# Power_Distribution_-_Solar_Sense_Telemet.net
KiCad netlist of a schematic drawn in Altium Designer
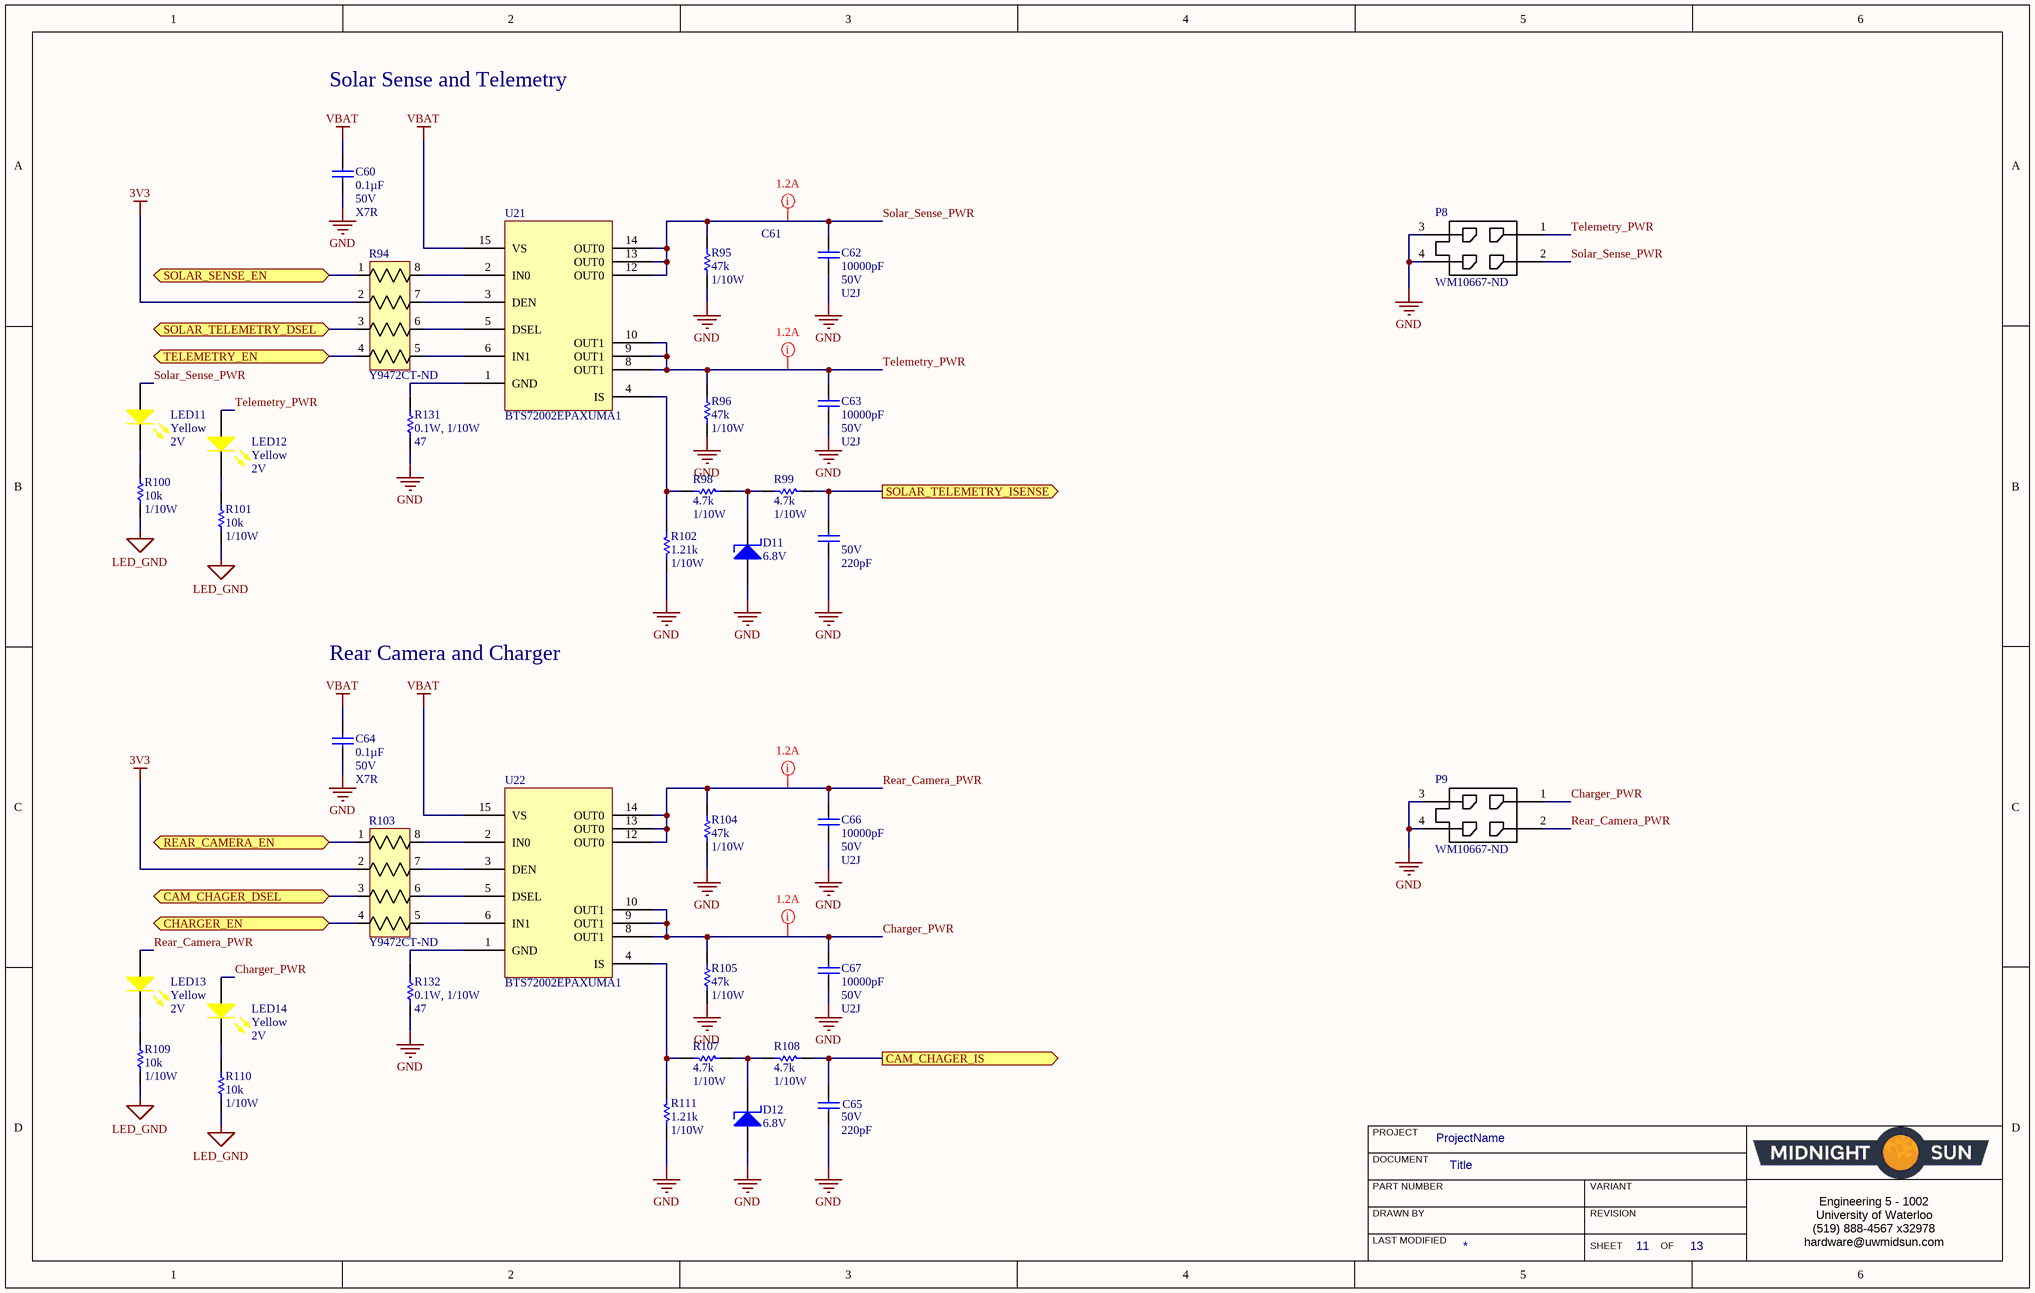
[diagram p0: Power Distribution - Solar Sense, Telemetry, Rear Camera, and Charger.SchDoc]

(export (version "E")
  (design (tool "Eeschema 10.0.6"))
  (components
    (comp (ref "C60")
      (value "CAP CER 0.1UF 50V 10% X7R 0603")
      (footprint "CAP, 0603")
      (description "0.10µF ±10% 50V Ceramic Capacitor X7R 0603 (1608 Metric)")
      (fields
        (field (name "TOLERANCE") "±10%")
        (field (name "CAPACITANCE") "0.1µF")
        (field (name "VOLTAGE") "50V")
        (field (name "TEMPERATURE COEFFICIENT") "X7R")
      )
      (libsource (lib "Schematic Diagrams") (part "CAP CER 0.1UF 50V 10% X7R 0603"))
    )
    (comp (ref "C61")
      (value "CAP CER 220PF 50V C0G/NP0 0603")
      (footprint "CAP, 0603")
      (description "220pF ±5% 50V Ceramic Capacitor C0G, NP0 0603 (1608 Metric)")
      (fields
        (field (name "MANUFACTURER") "KEMET")
        (field (name "TOLERANCE") "5%")
        (field (name "VOLTAGE RATING") "50V")
        (field (name "CAPACITANCE") "220pF")
      )
      (libsource (lib "Schematic Diagrams") (part "CAP CER 220PF 50V C0G/NP0 0603"))
    )
    (comp (ref "C62")
      (value "CAP CER 10nF 50V 5% X7R 0603")
      (footprint "CAP, 0603")
      (description "10000pF ±5% 50V Ceramic Capacitor U2J 0603 (1608 Metric)")
      (fields
        (field (name "TOLERANCE") "±5%")
        (field (name "CAPACITANCE") "10000pF")
        (field (name "VOLTAGE") "50V")
        (field (name "TEMPERATURE COEFFICIENT") "U2J")
      )
      (libsource (lib "Schematic Diagrams") (part "CAP CER 10nF 50V 5% X7R 0603"))
    )
    (comp (ref "C63")
      (value "CAP CER 10nF 50V 5% X7R 0603")
      (footprint "CAP, 0603")
      (description "10000pF ±5% 50V Ceramic Capacitor U2J 0603 (1608 Metric)")
      (fields
        (field (name "TOLERANCE") "±5%")
        (field (name "CAPACITANCE") "10000pF")
        (field (name "VOLTAGE") "50V")
        (field (name "TEMPERATURE COEFFICIENT") "U2J")
      )
      (libsource (lib "Schematic Diagrams") (part "CAP CER 10nF 50V 5% X7R 0603"))
    )
    (comp (ref "C64")
      (value "CAP CER 0.1UF 50V 10% X7R 0603")
      (footprint "CAP, 0603")
      (description "0.10µF ±10% 50V Ceramic Capacitor X7R 0603 (1608 Metric)")
      (fields
        (field (name "TOLERANCE") "±10%")
        (field (name "CAPACITANCE") "0.1µF")
        (field (name "VOLTAGE") "50V")
        (field (name "TEMPERATURE COEFFICIENT") "X7R")
      )
      (libsource (lib "Schematic Diagrams") (part "CAP CER 0.1UF 50V 10% X7R 0603"))
    )
    (comp (ref "C65")
      (value "CAP CER 220PF 50V C0G/NP0 0603")
      (footprint "CAP, 0603")
      (description "220pF ±5% 50V Ceramic Capacitor C0G, NP0 0603 (1608 Metric)")
      (fields
        (field (name "MANUFACTURER") "KEMET")
        (field (name "TOLERANCE") "5%")
        (field (name "VOLTAGE RATING") "50V")
        (field (name "CAPACITANCE") "220pF")
      )
      (libsource (lib "Schematic Diagrams") (part "CAP CER 220PF 50V C0G/NP0 0603"))
    )
    (comp (ref "C66")
      (value "CAP CER 10nF 50V 5% X7R 0603")
      (footprint "CAP, 0603")
      (description "10000pF ±5% 50V Ceramic Capacitor U2J 0603 (1608 Metric)")
      (fields
        (field (name "TOLERANCE") "±5%")
        (field (name "CAPACITANCE") "10000pF")
        (field (name "VOLTAGE") "50V")
        (field (name "TEMPERATURE COEFFICIENT") "U2J")
      )
      (libsource (lib "Schematic Diagrams") (part "CAP CER 10nF 50V 5% X7R 0603"))
    )
    (comp (ref "C67")
      (value "CAP CER 10nF 50V 5% X7R 0603")
      (footprint "CAP, 0603")
      (description "10000pF ±5% 50V Ceramic Capacitor U2J 0603 (1608 Metric)")
      (fields
        (field (name "TOLERANCE") "±5%")
        (field (name "CAPACITANCE") "10000pF")
        (field (name "VOLTAGE") "50V")
        (field (name "TEMPERATURE COEFFICIENT") "U2J")
      )
      (libsource (lib "Schematic Diagrams") (part "CAP CER 10nF 50V 5% X7R 0603"))
    )
    (comp (ref "D11")
      (value "6.8V")
      (footprint "DIODE SOD123")
      (description "Zener Diode 6.8V 500mW ±5% Surface Mount SOD-123")
      (fields (field (name "MANUFACTURER") "Diodes Incorporated") (field (name "TOLERANCE") "±5%"))
      (libsource (lib "Schematic Diagrams") (part "DIODE ZENER 6.8V 500MW SOD123"))
    )
    (comp (ref "D12")
      (value "6.8V")
      (footprint "DIODE SOD123")
      (description "Zener Diode 6.8V 500mW ±5% Surface Mount SOD-123")
      (fields (field (name "MANUFACTURER") "Diodes Incorporated") (field (name "TOLERANCE") "±5%"))
      (libsource (lib "Schematic Diagrams") (part "DIODE ZENER 6.8V 500MW SOD123"))
    )
    (comp (ref "LED11")
      (value "LED YELLOW CLEAR 2.1V 0603")
      (footprint "LED_0603")
      (description "Yellow 590nm LED Indication - Discrete 2V 0603 (1608 Metric)")
      (fields
        (field (name "MANUFACTURER") "Wurth Electronics Inc.")
        (field (name "MANUFACTURER PART NUMBER") "150060YS75000")
        (field (name "COLOR") "Yellow")
        (field (name "VOLTAGE - FORWARD (VF) (TYP)") "2V")
      )
      (libsource (lib "Schematic Diagrams") (part "LED YELLOW CLEAR 2.1V 0603"))
    )
    (comp (ref "LED12")
      (value "LED YELLOW CLEAR 2.1V 0603")
      (footprint "LED_0603")
      (description "Yellow 590nm LED Indication - Discrete 2V 0603 (1608 Metric)")
      (fields
        (field (name "MANUFACTURER") "Wurth Electronics Inc.")
        (field (name "MANUFACTURER PART NUMBER") "150060YS75000")
        (field (name "COLOR") "Yellow")
        (field (name "VOLTAGE - FORWARD (VF) (TYP)") "2V")
      )
      (libsource (lib "Schematic Diagrams") (part "LED YELLOW CLEAR 2.1V 0603"))
    )
    (comp (ref "LED13")
      (value "LED YELLOW CLEAR 2.1V 0603")
      (footprint "LED_0603")
      (description "Yellow 590nm LED Indication - Discrete 2V 0603 (1608 Metric)")
      (fields
        (field (name "MANUFACTURER") "Wurth Electronics Inc.")
        (field (name "MANUFACTURER PART NUMBER") "150060YS75000")
        (field (name "COLOR") "Yellow")
        (field (name "VOLTAGE - FORWARD (VF) (TYP)") "2V")
      )
      (libsource (lib "Schematic Diagrams") (part "LED YELLOW CLEAR 2.1V 0603"))
    )
    (comp (ref "LED14")
      (value "LED YELLOW CLEAR 2.1V 0603")
      (footprint "LED_0603")
      (description "Yellow 590nm LED Indication - Discrete 2V 0603 (1608 Metric)")
      (fields
        (field (name "MANUFACTURER") "Wurth Electronics Inc.")
        (field (name "MANUFACTURER PART NUMBER") "150060YS75000")
        (field (name "COLOR") "Yellow")
        (field (name "VOLTAGE - FORWARD (VF) (TYP)") "2V")
      )
      (libsource (lib "Schematic Diagrams") (part "LED YELLOW CLEAR 2.1V 0603"))
    )
    (comp (ref "P8")
      (value "CONN 4POS MICRO-FIT 3mm")
      (footprint "CONN 4POS MICROFIT (2x2)")
      (fields
        (field (name "MANUFACTURER") "Molex, LLC")
        (field (name "MANUFACTURER PART NUMBER") "430450427")
        (field (name "SUPPLIER PART NUMBER 1") "WM10667-ND")
      )
      (libsource (lib "Schematic Diagrams") (part "CONN 4POS MICRO-FIT 3mm"))
    )
    (comp (ref "P9")
      (value "CONN 4POS MICRO-FIT 3mm")
      (footprint "CONN 4POS MICROFIT (2x2)")
      (fields
        (field (name "MANUFACTURER") "Molex, LLC")
        (field (name "MANUFACTURER PART NUMBER") "430450427")
        (field (name "SUPPLIER PART NUMBER 1") "WM10667-ND")
      )
      (libsource (lib "Schematic Diagrams") (part "CONN 4POS MICRO-FIT 3mm"))
    )
    (comp (ref "R94")
      (value "RES ARRAY 4 RES 4.7K OHM 1206")
      (footprint "RES ARRAY 4RES 1206")
      (fields (field (name "TOLERANCE") "±5%") (field (name "SUPPLIER PART NUMBER 1") "Y9472CT-ND"))
      (libsource (lib "Schematic Diagrams") (part "RES ARRAY 4 RES 4.7K OHM 1206"))
    )
    (comp (ref "R95")
      (value "RES 47K OHM 1% 1/10W 0603")
      (footprint "RES, 0603")
      (description "47 kOhms ±1% 0.1W, 1/10W Chip Resistor 0603 (1608 Metric) Automotive AEC-Q200 Thick Film")
      (fields
        (field (name "MANUFACTURER") "Panasonic")
        (field (name "MANUFACTURER PART NUMBER") "ERJ3EKF4702V")
        (field (name "RESISTANCE") "47k")
        (field (name "POWER RATING") "1/10W")
      )
      (libsource (lib "Schematic Diagrams") (part "RES 47K OHM 1% 1/10W 0603"))
    )
    (comp (ref "R96")
      (value "RES 47K OHM 1% 1/10W 0603")
      (footprint "RES, 0603")
      (description "47 kOhms ±1% 0.1W, 1/10W Chip Resistor 0603 (1608 Metric) Automotive AEC-Q200 Thick Film")
      (fields
        (field (name "MANUFACTURER") "Panasonic")
        (field (name "MANUFACTURER PART NUMBER") "ERJ3EKF4702V")
        (field (name "RESISTANCE") "47k")
        (field (name "POWER RATING") "1/10W")
      )
      (libsource (lib "Schematic Diagrams") (part "RES 47K OHM 1% 1/10W 0603"))
    )
    (comp (ref "R98")
      (value "RES 4.7K OHM 1% 1/10W 0603")
      (footprint "RES, 0603")
      (description "4.7k Ohm ±1% 0.1W, 1/10W Chip Resistor 0603 (1608 Metric) Moisture Resistant Thick Film")
      (fields
        (field (name "TOLERANCE") "±1%")
        (field (name "RESISTANCE (OHMS)") "4.7k")
        (field (name "POWER (WATTS)") "1/10W")
      )
      (libsource (lib "Schematic Diagrams") (part "RES 4.7K OHM 1% 1/10W 0603"))
    )
    (comp (ref "R99")
      (value "RES 4.7K OHM 1% 1/10W 0603")
      (footprint "RES, 0603")
      (description "4.7k Ohm ±1% 0.1W, 1/10W Chip Resistor 0603 (1608 Metric) Moisture Resistant Thick Film")
      (fields
        (field (name "TOLERANCE") "±1%")
        (field (name "RESISTANCE (OHMS)") "4.7k")
        (field (name "POWER (WATTS)") "1/10W")
      )
      (libsource (lib "Schematic Diagrams") (part "RES 4.7K OHM 1% 1/10W 0603"))
    )
    (comp (ref "R100")
      (value "RES 10K OHM 1% 1/10W 0603")
      (footprint "RES, 0603")
      (description "RES SMD 10K OHM 1% 1/10W 0603")
      (fields
        (field (name "TOLERANCE") "±1%")
        (field (name "RESISTANCE") "10k")
        (field (name "POWER") "1/10W")
      )
      (libsource (lib "Schematic Diagrams") (part "RES 10K OHM 1% 1/10W 0603"))
    )
    (comp (ref "R101")
      (value "RES 10K OHM 1% 1/10W 0603")
      (footprint "RES, 0603")
      (description "RES SMD 10K OHM 1% 1/10W 0603")
      (fields
        (field (name "TOLERANCE") "±1%")
        (field (name "RESISTANCE") "10k")
        (field (name "POWER") "1/10W")
      )
      (libsource (lib "Schematic Diagrams") (part "RES 10K OHM 1% 1/10W 0603"))
    )
    (comp (ref "R102")
      (value "RES 1.21K OHM 1% 1/10W 0603")
      (footprint "RES, 0603")
      (description "1.21k Ohm ±1% 0.1W, 1/10W Chip Resistor 0603 (1608 Metric) Moisture Resistant Thick Film")
      (fields
        (field (name "TOLERANCE") "±1%")
        (field (name "RESISTANCE") "1.21k")
        (field (name "POWER") "1/10W")
      )
      (libsource (lib "Schematic Diagrams") (part "RES 1.21K OHM 1% 1/10W 0603"))
    )
    (comp (ref "R103")
      (value "RES ARRAY 4 RES 4.7K OHM 1206")
      (footprint "RES ARRAY 4RES 1206")
      (fields (field (name "TOLERANCE") "±5%") (field (name "SUPPLIER PART NUMBER 1") "Y9472CT-ND"))
      (libsource (lib "Schematic Diagrams") (part "RES ARRAY 4 RES 4.7K OHM 1206"))
    )
    (comp (ref "R104")
      (value "RES 47K OHM 1% 1/10W 0603")
      (footprint "RES, 0603")
      (description "47 kOhms ±1% 0.1W, 1/10W Chip Resistor 0603 (1608 Metric) Automotive AEC-Q200 Thick Film")
      (fields
        (field (name "MANUFACTURER") "Panasonic")
        (field (name "MANUFACTURER PART NUMBER") "ERJ3EKF4702V")
        (field (name "RESISTANCE") "47k")
        (field (name "POWER RATING") "1/10W")
      )
      (libsource (lib "Schematic Diagrams") (part "RES 47K OHM 1% 1/10W 0603"))
    )
    (comp (ref "R105")
      (value "RES 47K OHM 1% 1/10W 0603")
      (footprint "RES, 0603")
      (description "47 kOhms ±1% 0.1W, 1/10W Chip Resistor 0603 (1608 Metric) Automotive AEC-Q200 Thick Film")
      (fields
        (field (name "MANUFACTURER") "Panasonic")
        (field (name "MANUFACTURER PART NUMBER") "ERJ3EKF4702V")
        (field (name "RESISTANCE") "47k")
        (field (name "POWER RATING") "1/10W")
      )
      (libsource (lib "Schematic Diagrams") (part "RES 47K OHM 1% 1/10W 0603"))
    )
    (comp (ref "R107")
      (value "RES 4.7K OHM 1% 1/10W 0603")
      (footprint "RES, 0603")
      (description "4.7k Ohm ±1% 0.1W, 1/10W Chip Resistor 0603 (1608 Metric) Moisture Resistant Thick Film")
      (fields
        (field (name "TOLERANCE") "±1%")
        (field (name "RESISTANCE (OHMS)") "4.7k")
        (field (name "POWER (WATTS)") "1/10W")
      )
      (libsource (lib "Schematic Diagrams") (part "RES 4.7K OHM 1% 1/10W 0603"))
    )
    (comp (ref "R108")
      (value "RES 4.7K OHM 1% 1/10W 0603")
      (footprint "RES, 0603")
      (description "4.7k Ohm ±1% 0.1W, 1/10W Chip Resistor 0603 (1608 Metric) Moisture Resistant Thick Film")
      (fields
        (field (name "TOLERANCE") "±1%")
        (field (name "RESISTANCE (OHMS)") "4.7k")
        (field (name "POWER (WATTS)") "1/10W")
      )
      (libsource (lib "Schematic Diagrams") (part "RES 4.7K OHM 1% 1/10W 0603"))
    )
    (comp (ref "R109")
      (value "RES 10K OHM 1% 1/10W 0603")
      (footprint "RES, 0603")
      (description "RES SMD 10K OHM 1% 1/10W 0603")
      (fields
        (field (name "TOLERANCE") "±1%")
        (field (name "RESISTANCE") "10k")
        (field (name "POWER") "1/10W")
      )
      (libsource (lib "Schematic Diagrams") (part "RES 10K OHM 1% 1/10W 0603"))
    )
    (comp (ref "R110")
      (value "RES 10K OHM 1% 1/10W 0603")
      (footprint "RES, 0603")
      (description "RES SMD 10K OHM 1% 1/10W 0603")
      (fields
        (field (name "TOLERANCE") "±1%")
        (field (name "RESISTANCE") "10k")
        (field (name "POWER") "1/10W")
      )
      (libsource (lib "Schematic Diagrams") (part "RES 10K OHM 1% 1/10W 0603"))
    )
    (comp (ref "R111")
      (value "RES 1.21K OHM 1% 1/10W 0603")
      (footprint "RES, 0603")
      (description "1.21k Ohm ±1% 0.1W, 1/10W Chip Resistor 0603 (1608 Metric) Moisture Resistant Thick Film")
      (fields
        (field (name "TOLERANCE") "±1%")
        (field (name "RESISTANCE") "1.21k")
        (field (name "POWER") "1/10W")
      )
      (libsource (lib "Schematic Diagrams") (part "RES 1.21K OHM 1% 1/10W 0603"))
    )
    (comp (ref "R131")
      (value "RES SMD 47 OHM 1% 1/10W 0603")
      (footprint "RES, 0603")
      (fields
        (field (name "TOLERANCE") "±1%")
        (field (name "POWER (WATTS)") "0.1W, 1/10W")
        (field (name "VALUES") "47")
      )
      (libsource (lib "Schematic Diagrams") (part "RES SMD 47 OHM 1% 1/10W 0603"))
    )
    (comp (ref "R132")
      (value "RES SMD 47 OHM 1% 1/10W 0603")
      (footprint "RES, 0603")
      (fields
        (field (name "TOLERANCE") "±1%")
        (field (name "POWER (WATTS)") "0.1W, 1/10W")
        (field (name "VALUES") "47")
      )
      (libsource (lib "Schematic Diagrams") (part "RES SMD 47 OHM 1% 1/10W 0603"))
    )
    (comp (ref "U21")
      (value "IC LOAD SWITCH BTS7200-2EPA PG-TSDSO-14_1")
      (footprint "IC LOAD SWITCH PG-TSDSO-14-22")
      (description "Power Switch/Driver 1:1 N-Channel 1.2A PG-TSDSO-14-22")
      (fields
        (field (name "MANUFACTURER") "Infineon")
        (field (name "MANUFACTURER PART NUMBER") "BTS72002EPAXUMA1")
      )
      (libsource (lib "Schematic Diagrams") (part "IC LOAD SWITCH BTS7200-2EPA PG-TSDSO-14_1"))
    )
    (comp (ref "U22")
      (value "IC LOAD SWITCH BTS7200-2EPA PG-TSDSO-14_1")
      (footprint "IC LOAD SWITCH PG-TSDSO-14-22")
      (description "Power Switch/Driver 1:1 N-Channel 1.2A PG-TSDSO-14-22")
      (fields
        (field (name "MANUFACTURER") "Infineon")
        (field (name "MANUFACTURER PART NUMBER") "BTS72002EPAXUMA1")
      )
      (libsource (lib "Schematic Diagrams") (part "IC LOAD SWITCH BTS7200-2EPA PG-TSDSO-14_1"))
    )
  )
  (nets
    (net (code "1") (name "/CAM_CHAGER_DSEL") (class "Default")
      (node (ref "R103") (pin "3") (pinfunction "3_3") (pintype "passive"))
    )
    (net (code "2") (name "/CAM_CHAGER_IS") (class "Default")
      (node (ref "C65") (pin "1") (pinfunction "1_1") (pintype "passive"))
      (node (ref "R108") (pin "1") (pinfunction "1_1") (pintype "passive"))
    )
    (net (code "3") (name "/CHARGER_EN") (class "Default")
      (node (ref "R103") (pin "4") (pinfunction "4_4") (pintype "passive"))
    )
    (net (code "4") (name "/Charger_PWR") (class "Default")
      (node (ref "C67") (pin "1") (pinfunction "1_1") (pintype "passive"))
      (node (ref "LED14") (pin "1") (pinfunction "A_1") (pintype "passive"))
      (node (ref "P9") (pin "1") (pinfunction "1_1") (pintype "passive"))
      (node (ref "R105") (pin "1") (pinfunction "1_1") (pintype "passive"))
      (node (ref "U22") (pin "10") (pinfunction "OUT1_10") (pintype "passive"))
      (node (ref "U22") (pin "8") (pinfunction "OUT1_8") (pintype "passive"))
      (node (ref "U22") (pin "9") (pinfunction "OUT1_9") (pintype "passive"))
    )
    (net (code "5") (name "/REAR_CAMERA_EN") (class "Default")
      (node (ref "R103") (pin "1") (pinfunction "1_1") (pintype "passive"))
    )
    (net (code "6") (name "/Rear_Camera_PWR") (class "Default")
      (node (ref "C66") (pin "1") (pinfunction "1_1") (pintype "passive"))
      (node (ref "LED13") (pin "1") (pinfunction "A_1") (pintype "passive"))
      (node (ref "P9") (pin "2") (pinfunction "2_2") (pintype "passive"))
      (node (ref "R104") (pin "1") (pinfunction "1_1") (pintype "passive"))
      (node (ref "U22") (pin "12") (pinfunction "OUT0_12") (pintype "passive"))
      (node (ref "U22") (pin "13") (pinfunction "OUT0_13") (pintype "passive"))
      (node (ref "U22") (pin "14") (pinfunction "OUT0_14") (pintype "passive"))
    )
    (net (code "7") (name "/SOLAR_SENSE_EN") (class "Default")
      (node (ref "R94") (pin "1") (pinfunction "1_1") (pintype "passive"))
    )
    (net (code "8") (name "/SOLAR_TELEMETRY_DSEL") (class "Default")
      (node (ref "R94") (pin "3") (pinfunction "3_3") (pintype "passive"))
    )
    (net (code "9") (name "/SOLAR_TELEMETRY_ISENSE") (class "Default")
      (node (ref "C61") (pin "1") (pinfunction "1_1") (pintype "passive"))
      (node (ref "R99") (pin "1") (pinfunction "1_1") (pintype "passive"))
    )
    (net (code "10") (name "/Solar_Sense_PWR") (class "Default")
      (node (ref "C62") (pin "1") (pinfunction "1_1") (pintype "passive"))
      (node (ref "LED11") (pin "1") (pinfunction "A_1") (pintype "passive"))
      (node (ref "P8") (pin "2") (pinfunction "2_2") (pintype "passive"))
      (node (ref "R95") (pin "1") (pinfunction "1_1") (pintype "passive"))
      (node (ref "U21") (pin "12") (pinfunction "OUT0_12") (pintype "passive"))
      (node (ref "U21") (pin "13") (pinfunction "OUT0_13") (pintype "passive"))
      (node (ref "U21") (pin "14") (pinfunction "OUT0_14") (pintype "passive"))
    )
    (net (code "11") (name "/TELEMETRY_EN") (class "Default")
      (node (ref "R94") (pin "4") (pinfunction "4_4") (pintype "passive"))
    )
    (net (code "12") (name "/Telemetry_PWR") (class "Default")
      (node (ref "C63") (pin "1") (pinfunction "1_1") (pintype "passive"))
      (node (ref "LED12") (pin "1") (pinfunction "A_1") (pintype "passive"))
      (node (ref "P8") (pin "1") (pinfunction "1_1") (pintype "passive"))
      (node (ref "R96") (pin "1") (pinfunction "1_1") (pintype "passive"))
      (node (ref "U21") (pin "10") (pinfunction "OUT1_10") (pintype "passive"))
      (node (ref "U21") (pin "8") (pinfunction "OUT1_8") (pintype "passive"))
      (node (ref "U21") (pin "9") (pinfunction "OUT1_9") (pintype "passive"))
    )
    (net (code "13") (name "3V3") (class "Default")
      (node (ref "R103") (pin "2") (pinfunction "2_2") (pintype "passive"))
      (node (ref "R94") (pin "2") (pinfunction "2_2") (pintype "passive"))
    )
    (net (code "14") (name "GND") (class "Default")
      (node (ref "C60") (pin "2") (pinfunction "2_2") (pintype "passive"))
      (node (ref "C61") (pin "2") (pinfunction "2_2") (pintype "passive"))
      (node (ref "C62") (pin "2") (pinfunction "2_2") (pintype "passive"))
      (node (ref "C63") (pin "2") (pinfunction "2_2") (pintype "passive"))
      (node (ref "C64") (pin "2") (pinfunction "2_2") (pintype "passive"))
      (node (ref "C65") (pin "2") (pinfunction "2_2") (pintype "passive"))
      (node (ref "C66") (pin "2") (pinfunction "2_2") (pintype "passive"))
      (node (ref "C67") (pin "2") (pinfunction "2_2") (pintype "passive"))
      (node (ref "D11") (pin "2") (pinfunction "A_2") (pintype "passive"))
      (node (ref "D12") (pin "2") (pinfunction "A_2") (pintype "passive"))
      (node (ref "P8") (pin "3") (pinfunction "3_3") (pintype "passive"))
      (node (ref "P8") (pin "4") (pinfunction "4_4") (pintype "passive"))
      (node (ref "P9") (pin "3") (pinfunction "3_3") (pintype "passive"))
      (node (ref "P9") (pin "4") (pinfunction "4_4") (pintype "passive"))
      (node (ref "R102") (pin "2") (pinfunction "2_2") (pintype "passive"))
      (node (ref "R104") (pin "2") (pinfunction "2_2") (pintype "passive"))
      (node (ref "R105") (pin "2") (pinfunction "2_2") (pintype "passive"))
      (node (ref "R111") (pin "2") (pinfunction "2_2") (pintype "passive"))
      (node (ref "R131") (pin "2") (pinfunction "2_2") (pintype "passive"))
      (node (ref "R132") (pin "2") (pinfunction "2_2") (pintype "passive"))
      (node (ref "R95") (pin "2") (pinfunction "2_2") (pintype "passive"))
      (node (ref "R96") (pin "2") (pinfunction "2_2") (pintype "passive"))
    )
    (net (code "15") (name "LED_GND") (class "Default")
      (node (ref "R100") (pin "2") (pinfunction "2_2") (pintype "passive"))
      (node (ref "R101") (pin "2") (pinfunction "2_2") (pintype "passive"))
      (node (ref "R109") (pin "2") (pinfunction "2_2") (pintype "passive"))
      (node (ref "R110") (pin "2") (pinfunction "2_2") (pintype "passive"))
    )
    (net (code "16") (name "Net-(D11-K)") (class "Default")
      (node (ref "D11") (pin "1") (pinfunction "K_1") (pintype "passive"))
      (node (ref "R98") (pin "1") (pinfunction "1_1") (pintype "passive"))
      (node (ref "R99") (pin "2") (pinfunction "2_2") (pintype "passive"))
    )
    (net (code "17") (name "Net-(D12-K)") (class "Default")
      (node (ref "D12") (pin "1") (pinfunction "K_1") (pintype "passive"))
      (node (ref "R107") (pin "1") (pinfunction "1_1") (pintype "passive"))
      (node (ref "R108") (pin "2") (pinfunction "2_2") (pintype "passive"))
    )
    (net (code "18") (name "Net-(LED11-K)") (class "Default")
      (node (ref "LED11") (pin "2") (pinfunction "K_2") (pintype "passive"))
      (node (ref "R100") (pin "1") (pinfunction "1_1") (pintype "passive"))
    )
    (net (code "19") (name "Net-(LED12-K)") (class "Default")
      (node (ref "LED12") (pin "2") (pinfunction "K_2") (pintype "passive"))
      (node (ref "R101") (pin "1") (pinfunction "1_1") (pintype "passive"))
    )
    (net (code "20") (name "Net-(LED13-K)") (class "Default")
      (node (ref "LED13") (pin "2") (pinfunction "K_2") (pintype "passive"))
      (node (ref "R109") (pin "1") (pinfunction "1_1") (pintype "passive"))
    )
    (net (code "21") (name "Net-(LED14-K)") (class "Default")
      (node (ref "LED14") (pin "2") (pinfunction "K_2") (pintype "passive"))
      (node (ref "R110") (pin "1") (pinfunction "1_1") (pintype "passive"))
    )
    (net (code "22") (name "Net-(U21-DEN)") (class "Default")
      (node (ref "R94") (pin "7") (pinfunction "7_7") (pintype "passive"))
      (node (ref "U21") (pin "3") (pinfunction "DEN_3") (pintype "passive"))
    )
    (net (code "23") (name "Net-(U21-DSEL)") (class "Default")
      (node (ref "R94") (pin "6") (pinfunction "6_6") (pintype "passive"))
      (node (ref "U21") (pin "5") (pinfunction "DSEL_5") (pintype "passive"))
    )
    (net (code "24") (name "Net-(U21-GND)") (class "Default")
      (node (ref "R131") (pin "1") (pinfunction "1_1") (pintype "passive"))
      (node (ref "U21") (pin "1") (pinfunction "GND_1") (pintype "passive"))
    )
    (net (code "25") (name "Net-(U21-IN0)") (class "Default")
      (node (ref "R94") (pin "8") (pinfunction "8_8") (pintype "passive"))
      (node (ref "U21") (pin "2") (pinfunction "IN0_2") (pintype "passive"))
    )
    (net (code "26") (name "Net-(U21-IN1)") (class "Default")
      (node (ref "R94") (pin "5") (pinfunction "5_5") (pintype "passive"))
      (node (ref "U21") (pin "6") (pinfunction "IN1_6") (pintype "passive"))
    )
    (net (code "27") (name "Net-(U21-IS)") (class "Default")
      (node (ref "R102") (pin "1") (pinfunction "1_1") (pintype "passive"))
      (node (ref "R98") (pin "2") (pinfunction "2_2") (pintype "passive"))
      (node (ref "U21") (pin "4") (pinfunction "IS_4") (pintype "passive"))
    )
    (net (code "28") (name "Net-(U22-DEN)") (class "Default")
      (node (ref "R103") (pin "7") (pinfunction "7_7") (pintype "passive"))
      (node (ref "U22") (pin "3") (pinfunction "DEN_3") (pintype "passive"))
    )
    (net (code "29") (name "Net-(U22-DSEL)") (class "Default")
      (node (ref "R103") (pin "6") (pinfunction "6_6") (pintype "passive"))
      (node (ref "U22") (pin "5") (pinfunction "DSEL_5") (pintype "passive"))
    )
    (net (code "30") (name "Net-(U22-GND)") (class "Default")
      (node (ref "R132") (pin "1") (pinfunction "1_1") (pintype "passive"))
      (node (ref "U22") (pin "1") (pinfunction "GND_1") (pintype "passive"))
    )
    (net (code "31") (name "Net-(U22-IN0)") (class "Default")
      (node (ref "R103") (pin "8") (pinfunction "8_8") (pintype "passive"))
      (node (ref "U22") (pin "2") (pinfunction "IN0_2") (pintype "passive"))
    )
    (net (code "32") (name "Net-(U22-IN1)") (class "Default")
      (node (ref "R103") (pin "5") (pinfunction "5_5") (pintype "passive"))
      (node (ref "U22") (pin "6") (pinfunction "IN1_6") (pintype "passive"))
    )
    (net (code "33") (name "Net-(U22-IS)") (class "Default")
      (node (ref "R107") (pin "2") (pinfunction "2_2") (pintype "passive"))
      (node (ref "R111") (pin "1") (pinfunction "1_1") (pintype "passive"))
      (node (ref "U22") (pin "4") (pinfunction "IS_4") (pintype "passive"))
    )
    (net (code "34") (name "VBAT") (class "Default")
      (node (ref "C60") (pin "1") (pinfunction "1_1") (pintype "passive"))
      (node (ref "C64") (pin "1") (pinfunction "1_1") (pintype "passive"))
      (node (ref "U21") (pin "15") (pinfunction "VS_15") (pintype "passive"))
      (node (ref "U22") (pin "15") (pinfunction "VS_15") (pintype "passive"))
    )
  )
)
